# Stabilizator.net
KiCad netlist of a schematic drawn in Altium Designer
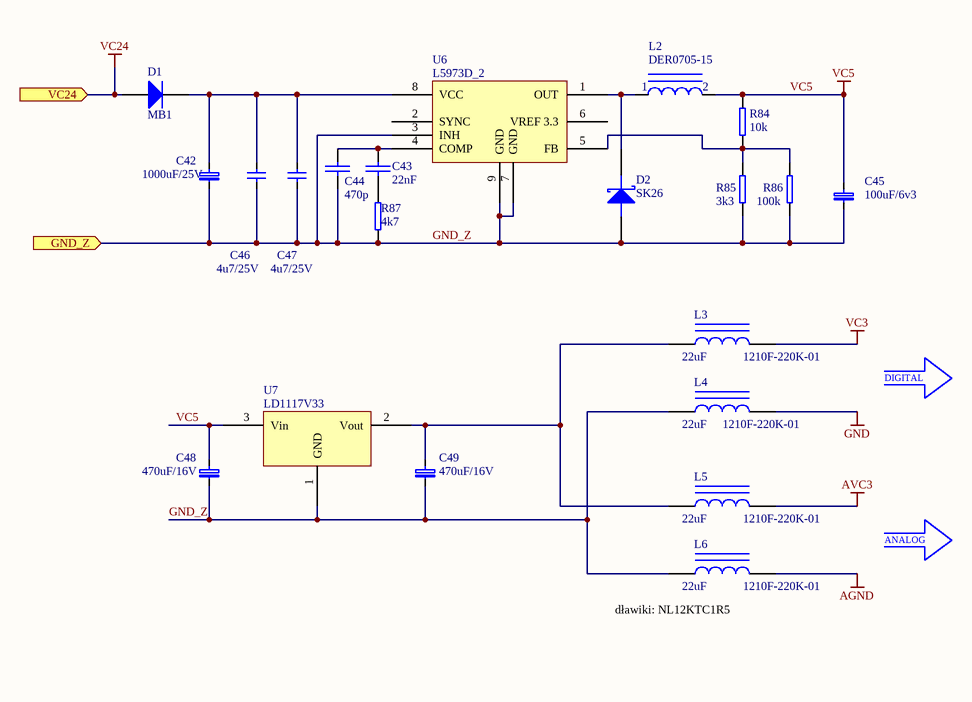
[diagram p0: Stabilizator.SchDoc]

(export (version "E")
  (design (tool "Eeschema 10.0.6"))
  (components
    (comp (ref "C42")
      (value "1000uF/25V")
      (footprint "RB-.2/.4")
      (description "KONDENSATOR ELEKTROLITYCZNY TANTALOWY SMD")
      (libsource (lib "*") (part "CAP_TANTAL_SMD"))
    )
    (comp (ref "C43")
      (value "22nF")
      (footprint "0603C")
      (description "Capacitor")
      (libsource (lib "") (part "CAP_1"))
    )
    (comp (ref "C44")
      (value "470p")
      (footprint "0603C")
      (description "Capacitor")
      (libsource (lib "") (part "CAP_1"))
    )
    (comp (ref "C45")
      (value "100uF/6v3")
      (footprint "CAP_C")
      (description "KONDENSATOR ELEKTROLITYCZNY TANTALOWY SMD")
      (libsource (lib "*") (part "CAP_TANTAL_SMD"))
    )
    (comp (ref "C46") (value "4u7/25V") (footprint "1206") (libsource (lib "*") (part "CAP")))
    (comp (ref "C47") (value "4u7/25V") (footprint "1206") (libsource (lib "*") (part "CAP")))
    (comp (ref "C48")
      (value "470uF/16V")
      (footprint "CAP_D")
      (description "KONDENSATOR ELEKTROLITYCZNY TANTALOWY SMD")
      (libsource (lib "*") (part "CAP_TANTAL_SMD"))
    )
    (comp (ref "C49")
      (value "470uF/16V")
      (footprint "CAP_D")
      (description "KONDENSATOR ELEKTROLITYCZNY TANTALOWY SMD")
      (libsource (lib "*") (part "CAP_TANTAL_SMD"))
    )
    (comp (ref "D1")
      (value "MB1")
      (footprint "RD5")
      (description "Default Diode")
      (fields (field (name "PUBLISHER") "Altium Limited"))
      (libsource (lib "Miscellaneous Devices") (part "Diode"))
    )
    (comp (ref "D2")
      (value "SK26")
      (footprint "RD5")
      (description "Schottky Diode")
      (libsource (lib "*") (part "DIODE SCHOTTKY"))
    )
    (comp (ref "L2") (value "DER0705-15") (footprint "DER0705_1") (libsource (lib "*") (part "CEWKA_1")))
    (comp (ref "L3")
      (value "1210F-220K-01")
      (footprint "IND_1812")
      (description "Magnetic-Core Inductor")
      (fields (field (name "ALTIUM_VALUE") "22uF") (field (name "PUBLISHER") "Altium Limited"))
      (libsource (lib "Miscellaneous Devices") (part "Inductor Iron"))
    )
    (comp (ref "L4")
      (value "1210F-220K-01")
      (footprint "IND_1812")
      (description "Magnetic-Core Inductor")
      (fields (field (name "ALTIUM_VALUE") "22uF") (field (name "PUBLISHER") "Altium Limited"))
      (libsource (lib "Miscellaneous Devices") (part "Inductor Iron"))
    )
    (comp (ref "L5")
      (value "1210F-220K-01")
      (footprint "IND_1812")
      (description "Magnetic-Core Inductor")
      (fields (field (name "ALTIUM_VALUE") "22uF") (field (name "PUBLISHER") "Altium Limited"))
      (libsource (lib "Miscellaneous Devices") (part "Inductor Iron"))
    )
    (comp (ref "L6")
      (value "1210F-220K-01")
      (footprint "IND_1812")
      (description "Magnetic-Core Inductor")
      (fields (field (name "ALTIUM_VALUE") "22uF") (field (name "PUBLISHER") "Altium Limited"))
      (libsource (lib "Miscellaneous Devices") (part "Inductor Iron"))
    )
    (comp (ref "R84") (value "10k") (footprint "0603R") (libsource (lib "*") (part "RES3")))
    (comp (ref "R85") (value "3k3") (footprint "0603R") (libsource (lib "*") (part "RES3")))
    (comp (ref "R86") (value "100k") (footprint "0603R") (libsource (lib "*") (part "RES3")))
    (comp (ref "R87") (value "4k7") (footprint "0603R") (libsource (lib "*") (part "RES3")))
    (comp (ref "U6") (value "L5973D_2") (footprint "SO8_M") (libsource (lib "ElhosSchLib") (part "L5973D_2")))
    (comp (ref "U7") (value "LD1117V33") (footprint "DPAK") (libsource (lib "*") (part "LD1117V33")))
  )
  (nets
    (net (code "1") (name "/GND_Z") (class "Default")
      (node (ref "C42") (pin "1") (pintype "passive"))
      (node (ref "C44") (pin "2") (pinfunction "2_2") (pintype "passive"))
      (node (ref "C45") (pin "1") (pintype "passive"))
      (node (ref "C46") (pin "1") (pintype "passive"))
      (node (ref "C47") (pin "1") (pintype "passive"))
      (node (ref "C48") (pin "1") (pintype "passive"))
      (node (ref "C49") (pin "1") (pintype "passive"))
      (node (ref "D2") (pin "A") (pinfunction "A_A") (pintype "passive"))
      (node (ref "L4") (pin "1") (pinfunction "1_1") (pintype "passive"))
      (node (ref "L6") (pin "1") (pinfunction "1_1") (pintype "passive"))
      (node (ref "R85") (pin "2") (pintype "passive"))
      (node (ref "R86") (pin "2") (pintype "passive"))
      (node (ref "R87") (pin "2") (pintype "passive"))
      (node (ref "U6") (pin "3") (pinfunction "INH_3") (pintype "passive"))
      (node (ref "U6") (pin "7") (pinfunction "GND_7") (pintype "passive"))
      (node (ref "U6") (pin "9") (pinfunction "GND_9") (pintype "passive"))
      (node (ref "U7") (pin "1") (pinfunction "GND_1") (pintype "passive"))
    )
    (net (code "2") (name "AGND") (class "Default")
      (node (ref "L6") (pin "2") (pinfunction "2_2") (pintype "passive"))
    )
    (net (code "3") (name "AVC3") (class "Default")
      (node (ref "L5") (pin "2") (pinfunction "2_2") (pintype "passive"))
    )
    (net (code "4") (name "GND") (class "Default")
      (node (ref "L4") (pin "2") (pinfunction "2_2") (pintype "passive"))
    )
    (net (code "5") (name "Net-(C43-Pad1)") (class "Default")
      (node (ref "C43") (pin "1") (pinfunction "1_1") (pintype "passive"))
      (node (ref "R87") (pin "1") (pintype "passive"))
    )
    (net (code "6") (name "Net-(U6-COMP)") (class "Default")
      (node (ref "C43") (pin "2") (pinfunction "2_2") (pintype "passive"))
      (node (ref "C44") (pin "1") (pinfunction "1_1") (pintype "passive"))
      (node (ref "U6") (pin "4") (pinfunction "COMP_4") (pintype "passive"))
    )
    (net (code "7") (name "Net-(U6-FB)") (class "Default")
      (node (ref "R84") (pin "2") (pintype "passive"))
      (node (ref "R85") (pin "1") (pintype "passive"))
      (node (ref "R86") (pin "1") (pintype "passive"))
      (node (ref "U6") (pin "5") (pinfunction "FB_5") (pintype "passive"))
    )
    (net (code "8") (name "Net-(U6-OUT)") (class "Default")
      (node (ref "D2") (pin "K") (pinfunction "K_K") (pintype "passive"))
      (node (ref "L2") (pin "1") (pintype "passive"))
      (node (ref "U6") (pin "1") (pinfunction "OUT_1") (pintype "passive"))
    )
    (net (code "9") (name "Net-(U6-VCC)") (class "Default")
      (node (ref "C42") (pin "2") (pintype "passive"))
      (node (ref "C46") (pin "2") (pintype "passive"))
      (node (ref "C47") (pin "2") (pintype "passive"))
      (node (ref "D1") (pin "K") (pinfunction "K_K") (pintype "passive"))
      (node (ref "U6") (pin "8") (pinfunction "VCC_8") (pintype "passive"))
    )
    (net (code "10") (name "Net-(U7-Vout)") (class "Default")
      (node (ref "C49") (pin "2") (pintype "passive"))
      (node (ref "L3") (pin "1") (pinfunction "1_1") (pintype "passive"))
      (node (ref "L5") (pin "1") (pinfunction "1_1") (pintype "passive"))
      (node (ref "U7") (pin "2") (pinfunction "Vout_2") (pintype "passive"))
    )
    (net (code "11") (name "VC3") (class "Default")
      (node (ref "L3") (pin "2") (pinfunction "2_2") (pintype "passive"))
    )
    (net (code "12") (name "VC5") (class "Default")
      (node (ref "C45") (pin "2") (pintype "passive"))
      (node (ref "C48") (pin "2") (pintype "passive"))
      (node (ref "L2") (pin "2") (pintype "passive"))
      (node (ref "R84") (pin "1") (pintype "passive"))
      (node (ref "U7") (pin "3") (pinfunction "Vin_3") (pintype "passive"))
    )
    (net (code "13") (name "VC24") (class "Default")
      (node (ref "D1") (pin "A") (pinfunction "A_A") (pintype "passive"))
    )
    (net (code "14") (name "unconnected-(U6-SYNC-Pad2)") (class "Default")
      (node (ref "U6") (pin "2") (pinfunction "SYNC_2") (pintype "passive"))
    )
    (net (code "15") (name "unconnected-(U6-VREF_3.3-Pad6)") (class "Default")
      (node (ref "U6") (pin "6") (pinfunction "VREF_3.3_6") (pintype "passive"))
    )
  )
)
